# 09_-_FPGA_IO_BANK_2A_2L.net
KiCad netlist of a schematic drawn in Altium Designer
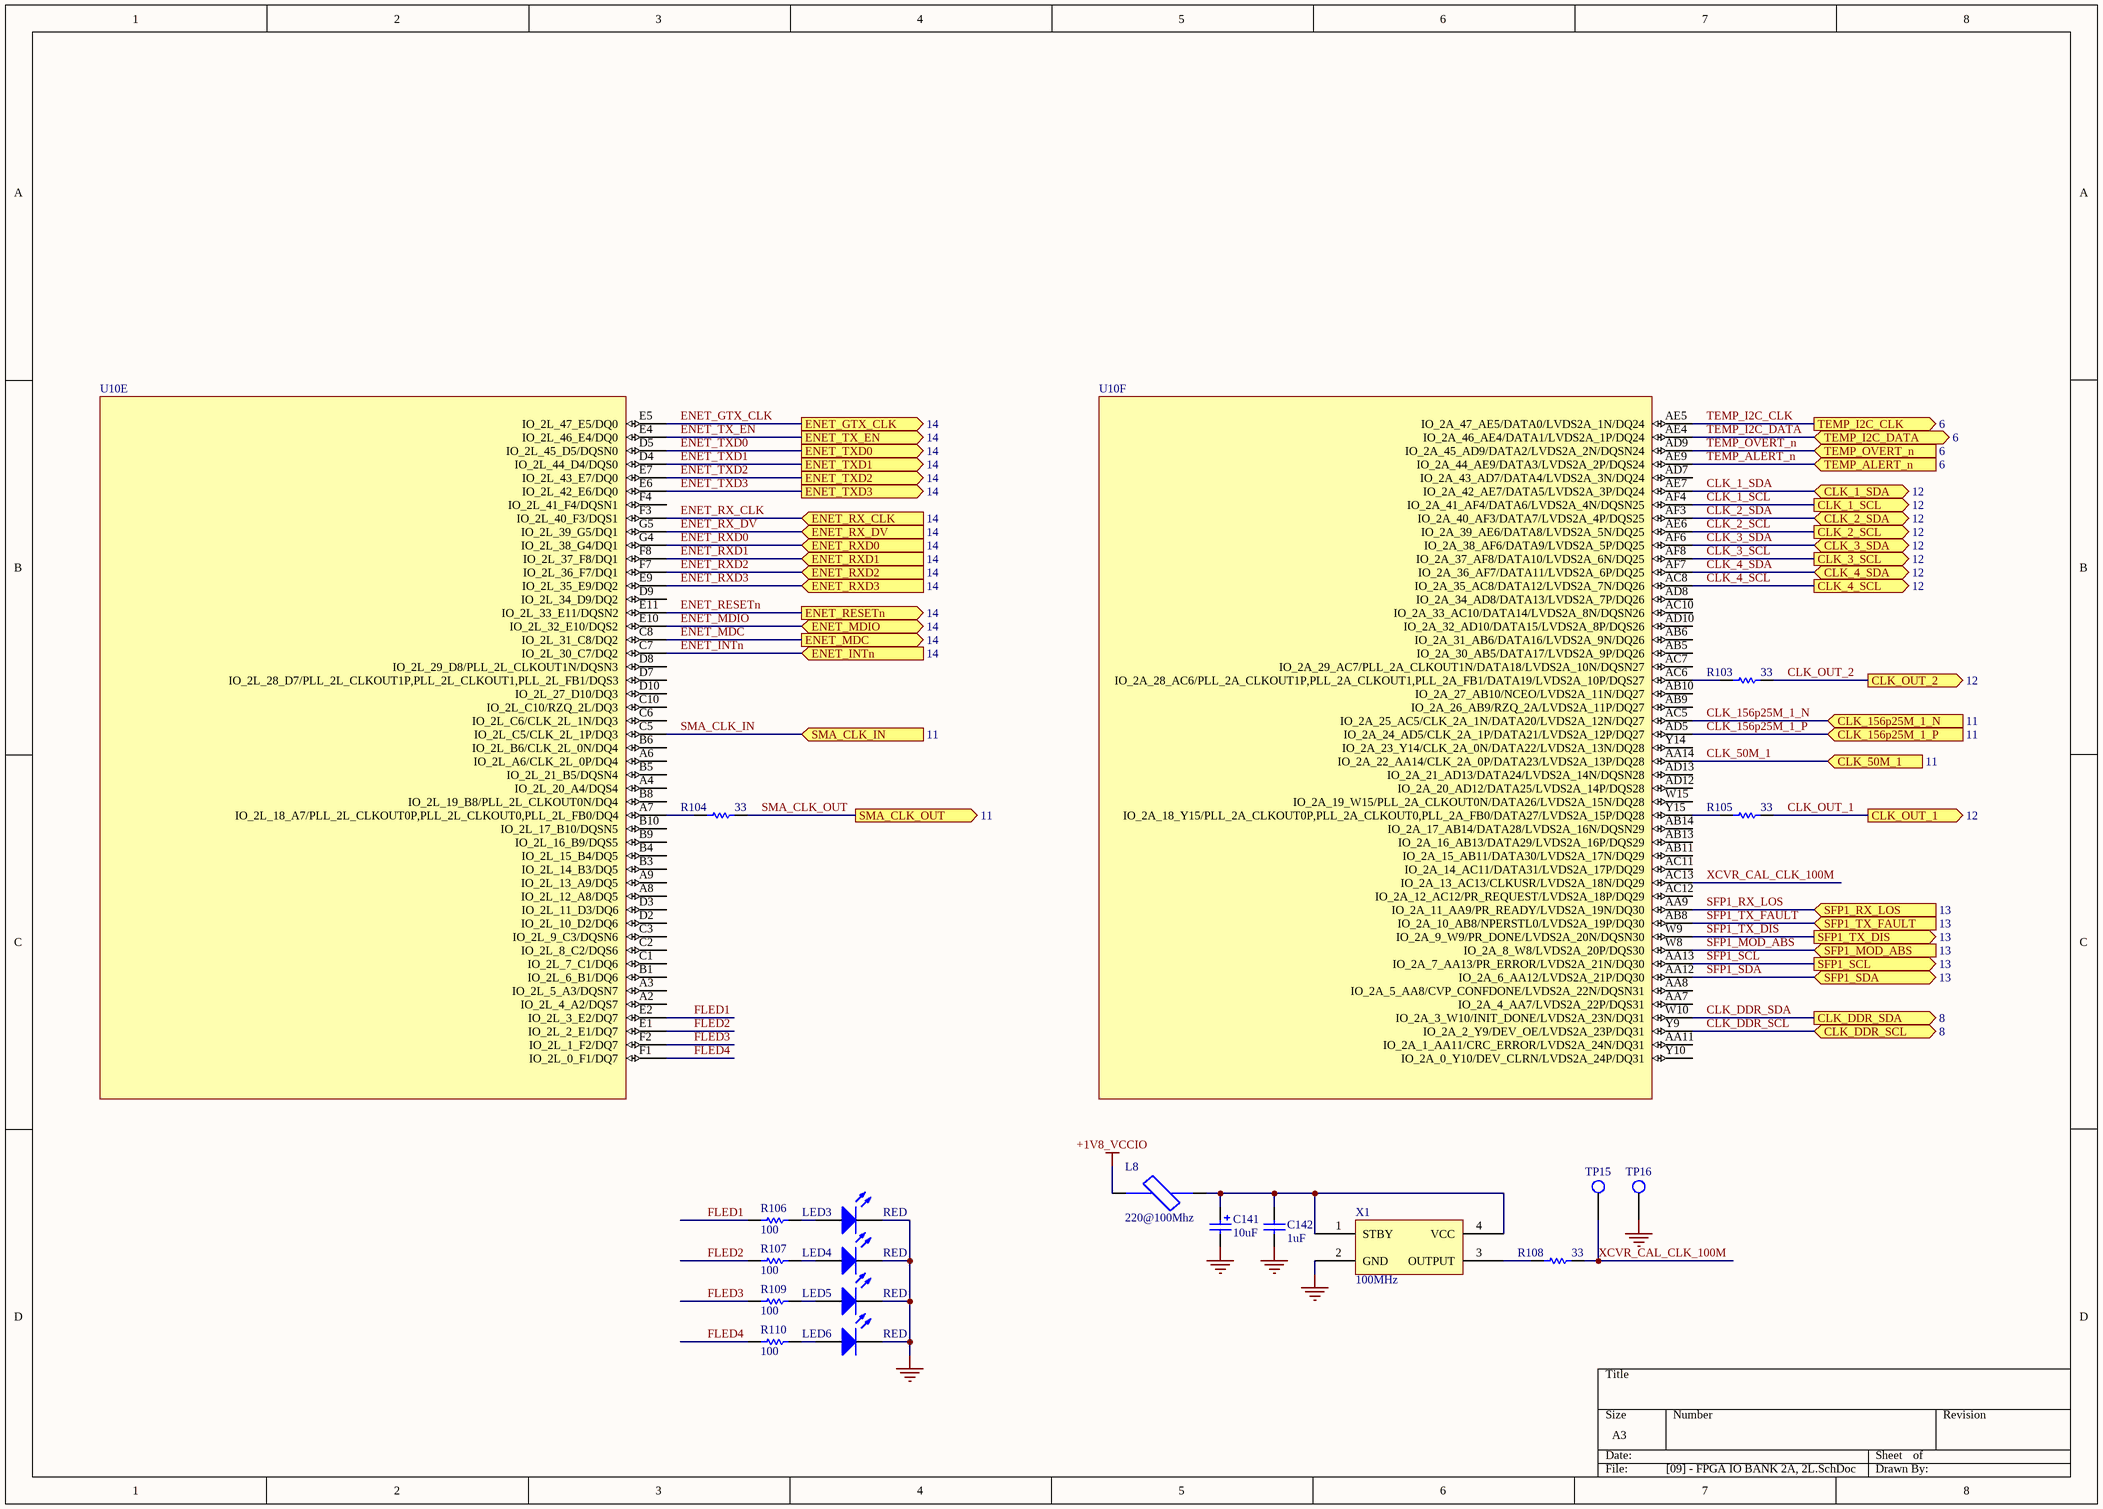
[diagram p0: [09] - FPGA IO BANK 2A, 2L.SchDoc]

(export (version "E")
  (design (tool "Eeschema 10.0.6"))
  (components
    (comp (ref "C141")
      (value "10uF")
      (footprint "TANT_B")
      (description "Tantalum Polarized Capacitor")
      (libsource (lib "Passive Components") (part "Cap Tant"))
    )
    (comp (ref "C142")
      (value "1uF")
      (footprint "0402_C")
      (description "Non-Pol SMD Capacitor")
      (libsource (lib "Passive Components") (part "Cap SMD"))
    )
    (comp (ref "L8")
      (value "220@100Mhz")
      (footprint "0805_L")
      (description "Ferrite Bead")
      (libsource (lib "Passive Components") (part "Ferrite Bead"))
    )
    (comp (ref "LED3")
      (value "RED")
      (footprint "LED_0805")
      (description "Typical LED")
      (libsource (lib "Common Components") (part "LED"))
    )
    (comp (ref "LED4")
      (value "RED")
      (footprint "LED_0805")
      (description "Typical LED")
      (libsource (lib "Common Components") (part "LED"))
    )
    (comp (ref "LED5")
      (value "RED")
      (footprint "LED_0805")
      (description "Typical LED")
      (libsource (lib "Common Components") (part "LED"))
    )
    (comp (ref "LED6")
      (value "RED")
      (footprint "LED_0805")
      (description "Typical LED")
      (libsource (lib "Common Components") (part "LED"))
    )
    (comp (ref "R103")
      (value "33")
      (footprint "0402_R")
      (description "SMD Resistor")
      (fields (field (name "TOLERANCE") "5%"))
      (libsource (lib "Passive Components") (part "Res SMD"))
    )
    (comp (ref "R104")
      (value "33")
      (footprint "0402_R")
      (description "SMD Resistor")
      (fields (field (name "TOLERANCE") "5%"))
      (libsource (lib "Passive Components") (part "Res SMD"))
    )
    (comp (ref "R105")
      (value "33")
      (footprint "0402_R")
      (description "SMD Resistor")
      (fields (field (name "TOLERANCE") "5%"))
      (libsource (lib "Passive Components") (part "Res SMD"))
    )
    (comp (ref "R106")
      (value "100")
      (footprint "0805_R")
      (description "SMD Resistor")
      (fields (field (name "TOLERANCE") "5%"))
      (libsource (lib "Passive Components") (part "Res SMD"))
    )
    (comp (ref "R107")
      (value "100")
      (footprint "0805_R")
      (description "SMD Resistor")
      (fields (field (name "TOLERANCE") "5%"))
      (libsource (lib "Passive Components") (part "Res SMD"))
    )
    (comp (ref "R108")
      (value "33")
      (footprint "0402_R")
      (description "SMD Resistor")
      (fields (field (name "TOLERANCE") "5%"))
      (libsource (lib "Passive Components") (part "Res SMD"))
    )
    (comp (ref "R109")
      (value "100")
      (footprint "0805_R")
      (description "SMD Resistor")
      (fields (field (name "TOLERANCE") "5%"))
      (libsource (lib "Passive Components") (part "Res SMD"))
    )
    (comp (ref "R110")
      (value "100")
      (footprint "0805_R")
      (description "SMD Resistor")
      (fields (field (name "TOLERANCE") "5%"))
      (libsource (lib "Passive Components") (part "Res SMD"))
    )
    (comp (ref "TP15")
      (value "Test Point")
      (footprint "PIN_1mm")
      (description "Test Point Footprint")
      (libsource (lib "Passive Components") (part "Test Point"))
    )
    (comp (ref "TP16")
      (value "Test Point")
      (footprint "PIN_1mm")
      (description "Test Point Footprint")
      (libsource (lib "Passive Components") (part "Test Point"))
    )
    (comp (ref "U10") (value "10AX016 F27") (footprint "FBGA672") (libsource (lib "") (part "10AX016_1")))
    (comp (ref "X1")
      (value "100MHz")
      (footprint "OSC_5X3.2")
      (description "Crystal Oscillator")
      (fields (field (name "MANUFACTURER PART NUM") "ECS-3518-1000-B-TR"))
      (libsource (lib "Common Components") (part "XTAL OSC"))
    )
  )
  (nets
    (net (code "1") (name "+1V8_VCCIO") (class "Default")
      (node (ref "L8") (pin "1") (pinfunction "1_1") (pintype "passive"))
    )
    (net (code "2") (name "/CLK_1_SCL") (class "Default")
      (node (ref "U10") (pin "AF4") (pinfunction "IO_2A_41_AF4/DATA6/LVDS2A_4N/DQSN25_AF4") (pintype "bidirectional"))
    )
    (net (code "3") (name "/CLK_1_SDA") (class "Default")
      (node (ref "U10") (pin "AE7") (pinfunction "IO_2A_42_AE7/DATA5/LVDS2A_3P/DQ24_AE7") (pintype "bidirectional"))
    )
    (net (code "4") (name "/CLK_2_SCL") (class "Default")
      (node (ref "U10") (pin "AE6") (pinfunction "IO_2A_39_AE6/DATA8/LVDS2A_5N/DQ25_AE6") (pintype "bidirectional"))
    )
    (net (code "5") (name "/CLK_2_SDA") (class "Default")
      (node (ref "U10") (pin "AF3") (pinfunction "IO_2A_40_AF3/DATA7/LVDS2A_4P/DQS25_AF3") (pintype "bidirectional"))
    )
    (net (code "6") (name "/CLK_3_SCL") (class "Default")
      (node (ref "U10") (pin "AF8") (pinfunction "IO_2A_37_AF8/DATA10/LVDS2A_6N/DQ25_AF8") (pintype "bidirectional"))
    )
    (net (code "7") (name "/CLK_3_SDA") (class "Default")
      (node (ref "U10") (pin "AF6") (pinfunction "IO_2A_38_AF6/DATA9/LVDS2A_5P/DQ25_AF6") (pintype "bidirectional"))
    )
    (net (code "8") (name "/CLK_4_SCL") (class "Default")
      (node (ref "U10") (pin "AC8") (pinfunction "IO_2A_35_AC8/DATA12/LVDS2A_7N/DQ26_AC8") (pintype "bidirectional"))
    )
    (net (code "9") (name "/CLK_4_SDA") (class "Default")
      (node (ref "U10") (pin "AF7") (pinfunction "IO_2A_36_AF7/DATA11/LVDS2A_6P/DQ25_AF7") (pintype "bidirectional"))
    )
    (net (code "10") (name "/CLK_50M_1") (class "Default")
      (node (ref "U10") (pin "AA14") (pinfunction "IO_2A_22_AA14/CLK_2A_0P/DATA23/LVDS2A_13P/DQ28_AA14") (pintype "bidirectional"))
    )
    (net (code "11") (name "/CLK_156p25M_1_N") (class "Default")
      (node (ref "U10") (pin "AC5") (pinfunction "IO_2A_25_AC5/CLK_2A_1N/DATA20/LVDS2A_12N/DQ27_AC5") (pintype "bidirectional"))
    )
    (net (code "12") (name "/CLK_156p25M_1_P") (class "Default")
      (node (ref "U10") (pin "AD5") (pinfunction "IO_2A_24_AD5/CLK_2A_1P/DATA21/LVDS2A_12P/DQ27_AD5") (pintype "bidirectional"))
    )
    (net (code "13") (name "/CLK_DDR_SCL") (class "Default")
      (node (ref "U10") (pin "Y9") (pinfunction "IO_2A_2_Y9/DEV_OE/LVDS2A_23P/DQ31_Y9") (pintype "bidirectional"))
    )
    (net (code "14") (name "/CLK_DDR_SDA") (class "Default")
      (node (ref "U10") (pin "W10") (pinfunction "IO_2A_3_W10/INIT_DONE/LVDS2A_23N/DQ31_W10") (pintype "bidirectional"))
    )
    (net (code "15") (name "/CLK_OUT_1") (class "Default")
      (node (ref "R105") (pin "2") (pinfunction "2_2") (pintype "passive"))
    )
    (net (code "16") (name "/CLK_OUT_2") (class "Default")
      (node (ref "R103") (pin "2") (pinfunction "2_2") (pintype "passive"))
    )
    (net (code "17") (name "/ENET_GTX_CLK") (class "Default")
      (node (ref "U10") (pin "E5") (pinfunction "IO_2L_47_E5/DQ0_E5") (pintype "bidirectional"))
    )
    (net (code "18") (name "/ENET_INTn") (class "Default")
      (node (ref "U10") (pin "C7") (pinfunction "IO_2L_30_C7/DQ2_C7") (pintype "bidirectional"))
    )
    (net (code "19") (name "/ENET_MDC") (class "Default")
      (node (ref "U10") (pin "C8") (pinfunction "IO_2L_31_C8/DQ2_C8") (pintype "bidirectional"))
    )
    (net (code "20") (name "/ENET_MDIO") (class "Default")
      (node (ref "U10") (pin "E10") (pinfunction "IO_2L_32_E10/DQS2_E10") (pintype "bidirectional"))
    )
    (net (code "21") (name "/ENET_RESETn") (class "Default")
      (node (ref "U10") (pin "E11") (pinfunction "IO_2L_33_E11/DQSN2_E11") (pintype "bidirectional"))
    )
    (net (code "22") (name "/ENET_RXD0") (class "Default")
      (node (ref "U10") (pin "G4") (pinfunction "IO_2L_38_G4/DQ1_G4") (pintype "bidirectional"))
    )
    (net (code "23") (name "/ENET_RXD1") (class "Default")
      (node (ref "U10") (pin "F8") (pinfunction "IO_2L_37_F8/DQ1_F8") (pintype "bidirectional"))
    )
    (net (code "24") (name "/ENET_RXD2") (class "Default")
      (node (ref "U10") (pin "F7") (pinfunction "IO_2L_36_F7/DQ1_F7") (pintype "bidirectional"))
    )
    (net (code "25") (name "/ENET_RXD3") (class "Default")
      (node (ref "U10") (pin "E9") (pinfunction "IO_2L_35_E9/DQ2_E9") (pintype "bidirectional"))
    )
    (net (code "26") (name "/ENET_RX_CLK") (class "Default")
      (node (ref "U10") (pin "F3") (pinfunction "IO_2L_40_F3/DQS1_F3") (pintype "bidirectional"))
    )
    (net (code "27") (name "/ENET_RX_DV") (class "Default")
      (node (ref "U10") (pin "G5") (pinfunction "IO_2L_39_G5/DQ1_G5") (pintype "bidirectional"))
    )
    (net (code "28") (name "/ENET_TXD0") (class "Default")
      (node (ref "U10") (pin "D5") (pinfunction "IO_2L_45_D5/DQSN0_D5") (pintype "bidirectional"))
    )
    (net (code "29") (name "/ENET_TXD1") (class "Default")
      (node (ref "U10") (pin "D4") (pinfunction "IO_2L_44_D4/DQS0_D4") (pintype "bidirectional"))
    )
    (net (code "30") (name "/ENET_TXD2") (class "Default")
      (node (ref "U10") (pin "E7") (pinfunction "IO_2L_43_E7/DQ0_E7") (pintype "bidirectional"))
    )
    (net (code "31") (name "/ENET_TXD3") (class "Default")
      (node (ref "U10") (pin "E6") (pinfunction "IO_2L_42_E6/DQ0_E6") (pintype "bidirectional"))
    )
    (net (code "32") (name "/ENET_TX_EN") (class "Default")
      (node (ref "U10") (pin "E4") (pinfunction "IO_2L_46_E4/DQ0_E4") (pintype "bidirectional"))
    )
    (net (code "33") (name "/FLED1") (class "Default")
      (node (ref "R106") (pin "2") (pinfunction "2_2") (pintype "passive"))
      (node (ref "U10") (pin "E2") (pinfunction "IO_2L_3_E2/DQ7_E2") (pintype "bidirectional"))
    )
    (net (code "34") (name "/FLED2") (class "Default")
      (node (ref "R107") (pin "2") (pinfunction "2_2") (pintype "passive"))
      (node (ref "U10") (pin "E1") (pinfunction "IO_2L_2_E1/DQ7_E1") (pintype "bidirectional"))
    )
    (net (code "35") (name "/FLED3") (class "Default")
      (node (ref "R109") (pin "2") (pinfunction "2_2") (pintype "passive"))
      (node (ref "U10") (pin "F2") (pinfunction "IO_2L_1_F2/DQ7_F2") (pintype "bidirectional"))
    )
    (net (code "36") (name "/FLED4") (class "Default")
      (node (ref "R110") (pin "2") (pinfunction "2_2") (pintype "passive"))
      (node (ref "U10") (pin "F1") (pinfunction "IO_2L_0_F1/DQ7_F1") (pintype "bidirectional"))
    )
    (net (code "37") (name "/SFP1_MOD_ABS") (class "Default")
      (node (ref "U10") (pin "W8") (pinfunction "IO_2A_8_W8/LVDS2A_20P/DQS30_W8") (pintype "bidirectional"))
    )
    (net (code "38") (name "/SFP1_RX_LOS") (class "Default")
      (node (ref "U10") (pin "AA9") (pinfunction "IO_2A_11_AA9/PR_READY/LVDS2A_19N/DQ30_AA9") (pintype "bidirectional"))
    )
    (net (code "39") (name "/SFP1_SCL") (class "Default")
      (node (ref "U10") (pin "AA13") (pinfunction "IO_2A_7_AA13/PR_ERROR/LVDS2A_21N/DQ30_AA13") (pintype "bidirectional"))
    )
    (net (code "40") (name "/SFP1_SDA") (class "Default")
      (node (ref "U10") (pin "AA12") (pinfunction "IO_2A_6_AA12/LVDS2A_21P/DQ30_AA12") (pintype "bidirectional"))
    )
    (net (code "41") (name "/SFP1_TX_DIS") (class "Default")
      (node (ref "U10") (pin "W9") (pinfunction "IO_2A_9_W9/PR_DONE/LVDS2A_20N/DQSN30_W9") (pintype "bidirectional"))
    )
    (net (code "42") (name "/SFP1_TX_FAULT") (class "Default")
      (node (ref "U10") (pin "AB8") (pinfunction "IO_2A_10_AB8/NPERSTL0/LVDS2A_19P/DQ30_AB8") (pintype "bidirectional"))
    )
    (net (code "43") (name "/SMA_CLK_IN") (class "Default")
      (node (ref "U10") (pin "C5") (pinfunction "IO_2L_C5/CLK_2L_1P/DQ3_C5") (pintype "bidirectional"))
    )
    (net (code "44") (name "/SMA_CLK_OUT") (class "Default")
      (node (ref "R104") (pin "2") (pinfunction "2_2") (pintype "passive"))
    )
    (net (code "45") (name "/TEMP_ALERT_n") (class "Default")
      (node (ref "U10") (pin "AE9") (pinfunction "IO_2A_44_AE9/DATA3/LVDS2A_2P/DQS24_AE9") (pintype "bidirectional"))
    )
    (net (code "46") (name "/TEMP_I2C_CLK") (class "Default")
      (node (ref "U10") (pin "AE5") (pinfunction "IO_2A_47_AE5/DATA0/LVDS2A_1N/DQ24_AE5") (pintype "bidirectional"))
    )
    (net (code "47") (name "/TEMP_I2C_DATA") (class "Default")
      (node (ref "U10") (pin "AE4") (pinfunction "IO_2A_46_AE4/DATA1/LVDS2A_1P/DQ24_AE4") (pintype "bidirectional"))
    )
    (net (code "48") (name "/TEMP_OVERT_n") (class "Default")
      (node (ref "U10") (pin "AD9") (pinfunction "IO_2A_45_AD9/DATA2/LVDS2A_2N/DQSN24_AD9") (pintype "bidirectional"))
    )
    (net (code "49") (name "/XCVR_CAL_CLK_100M") (class "Default")
      (node (ref "R108") (pin "2") (pinfunction "2_2") (pintype "passive"))
      (node (ref "TP15") (pin "1") (pinfunction "1_1") (pintype "passive"))
      (node (ref "U10") (pin "AC13") (pinfunction "IO_2A_13_AC13/CLKUSR/LVDS2A_18N/DQ29_AC13") (pintype "bidirectional"))
    )
    (net (code "50") (name "GND") (class "Default")
      (node (ref "C141") (pin "2") (pinfunction "2_2") (pintype "passive"))
      (node (ref "C142") (pin "1") (pinfunction "1_1") (pintype "passive"))
      (node (ref "LED3") (pin "2") (pinfunction "K_2") (pintype "passive"))
      (node (ref "LED4") (pin "2") (pinfunction "K_2") (pintype "passive"))
      (node (ref "LED5") (pin "2") (pinfunction "K_2") (pintype "passive"))
      (node (ref "LED6") (pin "2") (pinfunction "K_2") (pintype "passive"))
      (node (ref "TP16") (pin "1") (pinfunction "1_1") (pintype "passive"))
      (node (ref "X1") (pin "2") (pinfunction "GND_2") (pintype "passive"))
    )
    (net (code "51") (name "Net-(LED3-A)") (class "Default")
      (node (ref "LED3") (pin "1") (pinfunction "A_1") (pintype "passive"))
      (node (ref "R106") (pin "1") (pinfunction "1_1") (pintype "passive"))
    )
    (net (code "52") (name "Net-(LED4-A)") (class "Default")
      (node (ref "LED4") (pin "1") (pinfunction "A_1") (pintype "passive"))
      (node (ref "R107") (pin "1") (pinfunction "1_1") (pintype "passive"))
    )
    (net (code "53") (name "Net-(LED5-A)") (class "Default")
      (node (ref "LED5") (pin "1") (pinfunction "A_1") (pintype "passive"))
      (node (ref "R109") (pin "1") (pinfunction "1_1") (pintype "passive"))
    )
    (net (code "54") (name "Net-(LED6-A)") (class "Default")
      (node (ref "LED6") (pin "1") (pinfunction "A_1") (pintype "passive"))
      (node (ref "R110") (pin "1") (pinfunction "1_1") (pintype "passive"))
    )
    (net (code "55") (name "Net-(U10E-IO_2L_18_A7{slash}PLL_2L_CLKOUT0P,PLL_2L_CLKOUT0,PLL_2L_FB0{slash}DQ4)") (class "Default")
      (node (ref "R104") (pin "1") (pinfunction "1_1") (pintype "passive"))
      (node (ref "U10") (pin "A7") (pinfunction "IO_2L_18_A7/PLL_2L_CLKOUT0P,PLL_2L_CLKOUT0,PLL_2L_FB0/DQ4_A7") (pintype "bidirectional"))
    )
    (net (code "56") (name "Net-(U10F-IO_2A_18_Y15{slash}PLL_2A_CLKOUT0P,PLL_2A_CLKOUT0,PLL_2A_FB0{slash}DATA27{slash}LVDS2A_15P{slash}DQ28)") (class "Default")
      (node (ref "R105") (pin "1") (pinfunction "1_1") (pintype "passive"))
      (node (ref "U10") (pin "Y15") (pinfunction "IO_2A_18_Y15/PLL_2A_CLKOUT0P,PLL_2A_CLKOUT0,PLL_2A_FB0/DATA27/LVDS2A_15P/DQ28_Y15") (pintype "bidirectional"))
    )
    (net (code "57") (name "Net-(U10F-IO_2A_28_AC6{slash}PLL_2A_CLKOUT1P,PLL_2A_CLKOUT1,PLL_2A_FB1{slash}DATA19{slash}LVDS2A_10P{slash}DQS27)") (class "Default")
      (node (ref "R103") (pin "1") (pinfunction "1_1") (pintype "passive"))
      (node (ref "U10") (pin "AC6") (pinfunction "IO_2A_28_AC6/PLL_2A_CLKOUT1P,PLL_2A_CLKOUT1,PLL_2A_FB1/DATA19/LVDS2A_10P/DQS27_AC6") (pintype "bidirectional"))
    )
    (net (code "58") (name "Net-(X1-OUTPUT)") (class "Default")
      (node (ref "R108") (pin "1") (pinfunction "1_1") (pintype "passive"))
      (node (ref "X1") (pin "3") (pinfunction "OUTPUT_3") (pintype "passive"))
    )
    (net (code "59") (name "Net-(X1-STBY)") (class "Default")
      (node (ref "C141") (pin "1") (pinfunction "1_1") (pintype "passive"))
      (node (ref "C142") (pin "2") (pinfunction "2_2") (pintype "passive"))
      (node (ref "L8") (pin "2") (pinfunction "2_2") (pintype "passive"))
      (node (ref "X1") (pin "1") (pinfunction "STBY_1") (pintype "passive"))
      (node (ref "X1") (pin "4") (pinfunction "VCC_4") (pintype "passive"))
    )
    (net (code "60") (name "unconnected-(U10E-IO_2L_4_A2{slash}DQS7-PadA2)") (class "Default")
      (node (ref "U10") (pin "A2") (pinfunction "IO_2L_4_A2/DQS7_A2") (pintype "bidirectional"))
    )
    (net (code "61") (name "unconnected-(U10E-IO_2L_5_A3{slash}DQSN7-PadA3)") (class "Default")
      (node (ref "U10") (pin "A3") (pinfunction "IO_2L_5_A3/DQSN7_A3") (pintype "bidirectional"))
    )
    (net (code "62") (name "unconnected-(U10E-IO_2L_6_B1{slash}DQ6-PadB1)") (class "Default")
      (node (ref "U10") (pin "B1") (pinfunction "IO_2L_6_B1/DQ6_B1") (pintype "bidirectional"))
    )
    (net (code "63") (name "unconnected-(U10E-IO_2L_7_C1{slash}DQ6-PadC1)") (class "Default")
      (node (ref "U10") (pin "C1") (pinfunction "IO_2L_7_C1/DQ6_C1") (pintype "bidirectional"))
    )
    (net (code "64") (name "unconnected-(U10E-IO_2L_8_C2{slash}DQS6-PadC2)") (class "Default")
      (node (ref "U10") (pin "C2") (pinfunction "IO_2L_8_C2/DQS6_C2") (pintype "bidirectional"))
    )
    (net (code "65") (name "unconnected-(U10E-IO_2L_9_C3{slash}DQSN6-PadC3)") (class "Default")
      (node (ref "U10") (pin "C3") (pinfunction "IO_2L_9_C3/DQSN6_C3") (pintype "bidirectional"))
    )
    (net (code "66") (name "unconnected-(U10E-IO_2L_10_D2{slash}DQ6-PadD2)") (class "Default")
      (node (ref "U10") (pin "D2") (pinfunction "IO_2L_10_D2/DQ6_D2") (pintype "bidirectional"))
    )
    (net (code "67") (name "unconnected-(U10E-IO_2L_11_D3{slash}DQ6-PadD3)") (class "Default")
      (node (ref "U10") (pin "D3") (pinfunction "IO_2L_11_D3/DQ6_D3") (pintype "bidirectional"))
    )
    (net (code "68") (name "unconnected-(U10E-IO_2L_12_A8{slash}DQ5-PadA8)") (class "Default")
      (node (ref "U10") (pin "A8") (pinfunction "IO_2L_12_A8/DQ5_A8") (pintype "bidirectional"))
    )
    (net (code "69") (name "unconnected-(U10E-IO_2L_13_A9{slash}DQ5-PadA9)") (class "Default")
      (node (ref "U10") (pin "A9") (pinfunction "IO_2L_13_A9/DQ5_A9") (pintype "bidirectional"))
    )
    (net (code "70") (name "unconnected-(U10E-IO_2L_14_B3{slash}DQ5-PadB3)") (class "Default")
      (node (ref "U10") (pin "B3") (pinfunction "IO_2L_14_B3/DQ5_B3") (pintype "bidirectional"))
    )
    (net (code "71") (name "unconnected-(U10E-IO_2L_15_B4{slash}DQ5-PadB4)") (class "Default")
      (node (ref "U10") (pin "B4") (pinfunction "IO_2L_15_B4/DQ5_B4") (pintype "bidirectional"))
    )
    (net (code "72") (name "unconnected-(U10E-IO_2L_16_B9{slash}DQS5-PadB9)") (class "Default")
      (node (ref "U10") (pin "B9") (pinfunction "IO_2L_16_B9/DQS5_B9") (pintype "bidirectional"))
    )
    (net (code "73") (name "unconnected-(U10E-IO_2L_17_B10{slash}DQSN5-PadB10)") (class "Default")
      (node (ref "U10") (pin "B10") (pinfunction "IO_2L_17_B10/DQSN5_B10") (pintype "bidirectional"))
    )
    (net (code "74") (name "unconnected-(U10E-IO_2L_19_B8{slash}PLL_2L_CLKOUT0N{slash}DQ4-PadB8)") (class "Default")
      (node (ref "U10") (pin "B8") (pinfunction "IO_2L_19_B8/PLL_2L_CLKOUT0N/DQ4_B8") (pintype "bidirectional"))
    )
    (net (code "75") (name "unconnected-(U10E-IO_2L_20_A4{slash}DQS4-PadA4)") (class "Default")
      (node (ref "U10") (pin "A4") (pinfunction "IO_2L_20_A4/DQS4_A4") (pintype "bidirectional"))
    )
    (net (code "76") (name "unconnected-(U10E-IO_2L_21_B5{slash}DQSN4-PadB5)") (class "Default")
      (node (ref "U10") (pin "B5") (pinfunction "IO_2L_21_B5/DQSN4_B5") (pintype "bidirectional"))
    )
    (net (code "77") (name "unconnected-(U10E-IO_2L_27_D10{slash}DQ3-PadD10)") (class "Default")
      (node (ref "U10") (pin "D10") (pinfunction "IO_2L_27_D10/DQ3_D10") (pintype "bidirectional"))
    )
    (net (code "78") (name "unconnected-(U10E-IO_2L_28_D7{slash}PLL_2L_CLKOUT1P,PLL_2L_CLKOUT1,PLL_2L_FB1{slash}DQS3-PadD7)") (class "Default")
      (node (ref "U10") (pin "D7") (pinfunction "IO_2L_28_D7/PLL_2L_CLKOUT1P,PLL_2L_CLKOUT1,PLL_2L_FB1/DQS3_D7") (pintype "bidirectional"))
    )
    (net (code "79") (name "unconnected-(U10E-IO_2L_29_D8{slash}PLL_2L_CLKOUT1N{slash}DQSN3-PadD8)") (class "Default")
      (node (ref "U10") (pin "D8") (pinfunction "IO_2L_29_D8/PLL_2L_CLKOUT1N/DQSN3_D8") (pintype "bidirectional"))
    )
    (net (code "80") (name "unconnected-(U10E-IO_2L_34_D9{slash}DQ2-PadD9)") (class "Default")
      (node (ref "U10") (pin "D9") (pinfunction "IO_2L_34_D9/DQ2_D9") (pintype "bidirectional"))
    )
    (net (code "81") (name "unconnected-(U10E-IO_2L_41_F4{slash}DQSN1-PadF4)") (class "Default")
      (node (ref "U10") (pin "F4") (pinfunction "IO_2L_41_F4/DQSN1_F4") (pintype "bidirectional"))
    )
    (net (code "82") (name "unconnected-(U10E-IO_2L_A6{slash}CLK_2L_0P{slash}DQ4-PadA6)") (class "Default")
      (node (ref "U10") (pin "A6") (pinfunction "IO_2L_A6/CLK_2L_0P/DQ4_A6") (pintype "bidirectional"))
    )
    (net (code "83") (name "unconnected-(U10E-IO_2L_B6{slash}CLK_2L_0N{slash}DQ4-PadB6)") (class "Default")
      (node (ref "U10") (pin "B6") (pinfunction "IO_2L_B6/CLK_2L_0N/DQ4_B6") (pintype "bidirectional"))
    )
    (net (code "84") (name "unconnected-(U10E-IO_2L_C6{slash}CLK_2L_1N{slash}DQ3-PadC6)") (class "Default")
      (node (ref "U10") (pin "C6") (pinfunction "IO_2L_C6/CLK_2L_1N/DQ3_C6") (pintype "bidirectional"))
    )
    (net (code "85") (name "unconnected-(U10E-IO_2L_C10{slash}RZQ_2L{slash}DQ3-PadC10)") (class "Default")
      (node (ref "U10") (pin "C10") (pinfunction "IO_2L_C10/RZQ_2L/DQ3_C10") (pintype "bidirectional"))
    )
    (net (code "86") (name "unconnected-(U10F-IO_2A_0_Y10{slash}DEV_CLRN{slash}LVDS2A_24P{slash}DQ31-PadY10)") (class "Default")
      (node (ref "U10") (pin "Y10") (pinfunction "IO_2A_0_Y10/DEV_CLRN/LVDS2A_24P/DQ31_Y10") (pintype "bidirectional"))
    )
    (net (code "87") (name "unconnected-(U10F-IO_2A_1_AA11{slash}CRC_ERROR{slash}LVDS2A_24N{slash}DQ31-PadAA11)") (class "Default")
      (node (ref "U10") (pin "AA11") (pinfunction "IO_2A_1_AA11/CRC_ERROR/LVDS2A_24N/DQ31_AA11") (pintype "bidirectional"))
    )
    (net (code "88") (name "unconnected-(U10F-IO_2A_4_AA7{slash}LVDS2A_22P{slash}DQS31-PadAA7)") (class "Default")
      (node (ref "U10") (pin "AA7") (pinfunction "IO_2A_4_AA7/LVDS2A_22P/DQS31_AA7") (pintype "bidirectional"))
    )
    (net (code "89") (name "unconnected-(U10F-IO_2A_5_AA8{slash}CVP_CONFDONE{slash}LVDS2A_22N{slash}DQSN31-PadAA8)") (class "Default")
      (node (ref "U10") (pin "AA8") (pinfunction "IO_2A_5_AA8/CVP_CONFDONE/LVDS2A_22N/DQSN31_AA8") (pintype "bidirectional"))
    )
    (net (code "90") (name "unconnected-(U10F-IO_2A_12_AC12{slash}PR_REQUEST{slash}LVDS2A_18P{slash}DQ29-PadAC12)") (class "Default")
      (node (ref "U10") (pin "AC12") (pinfunction "IO_2A_12_AC12/PR_REQUEST/LVDS2A_18P/DQ29_AC12") (pintype "bidirectional"))
    )
    (net (code "91") (name "unconnected-(U10F-IO_2A_14_AC11{slash}DATA31{slash}LVDS2A_17P{slash}DQ29-PadAC11)") (class "Default")
      (node (ref "U10") (pin "AC11") (pinfunction "IO_2A_14_AC11/DATA31/LVDS2A_17P/DQ29_AC11") (pintype "bidirectional"))
    )
    (net (code "92") (name "unconnected-(U10F-IO_2A_15_AB11{slash}DATA30{slash}LVDS2A_17N{slash}DQ29-PadAB11)") (class "Default")
      (node (ref "U10") (pin "AB11") (pinfunction "IO_2A_15_AB11/DATA30/LVDS2A_17N/DQ29_AB11") (pintype "bidirectional"))
    )
    (net (code "93") (name "unconnected-(U10F-IO_2A_16_AB13{slash}DATA29{slash}LVDS2A_16P{slash}DQS29-PadAB13)") (class "Default")
      (node (ref "U10") (pin "AB13") (pinfunction "IO_2A_16_AB13/DATA29/LVDS2A_16P/DQS29_AB13") (pintype "bidirectional"))
    )
    (net (code "94") (name "unconnected-(U10F-IO_2A_17_AB14{slash}DATA28{slash}LVDS2A_16N{slash}DQSN29-PadAB14)") (class "Default")
      (node (ref "U10") (pin "AB14") (pinfunction "IO_2A_17_AB14/DATA28/LVDS2A_16N/DQSN29_AB14") (pintype "bidirectional"))
    )
    (net (code "95") (name "unconnected-(U10F-IO_2A_19_W15{slash}PLL_2A_CLKOUT0N{slash}DATA26{slash}LVDS2A_15N{slash}DQ28-PadW15)") (class "Default")
      (node (ref "U10") (pin "W15") (pinfunction "IO_2A_19_W15/PLL_2A_CLKOUT0N/DATA26/LVDS2A_15N/DQ28_W15") (pintype "bidirectional"))
    )
    (net (code "96") (name "unconnected-(U10F-IO_2A_20_AD12{slash}DATA25{slash}LVDS2A_14P{slash}DQS28-PadAD12)") (class "Default")
      (node (ref "U10") (pin "AD12") (pinfunction "IO_2A_20_AD12/DATA25/LVDS2A_14P/DQS28_AD12") (pintype "bidirectional"))
    )
    (net (code "97") (name "unconnected-(U10F-IO_2A_21_AD13{slash}DATA24{slash}LVDS2A_14N{slash}DQSN28-PadAD13)") (class "Default")
      (node (ref "U10") (pin "AD13") (pinfunction "IO_2A_21_AD13/DATA24/LVDS2A_14N/DQSN28_AD13") (pintype "bidirectional"))
    )
    (net (code "98") (name "unconnected-(U10F-IO_2A_23_Y14{slash}CLK_2A_0N{slash}DATA22{slash}LVDS2A_13N{slash}DQ28-PadY14)") (class "Default")
      (node (ref "U10") (pin "Y14") (pinfunction "IO_2A_23_Y14/CLK_2A_0N/DATA22/LVDS2A_13N/DQ28_Y14") (pintype "bidirectional"))
    )
    (net (code "99") (name "unconnected-(U10F-IO_2A_26_AB9{slash}RZQ_2A{slash}LVDS2A_11P{slash}DQ27-PadAB9)") (class "Default")
      (node (ref "U10") (pin "AB9") (pinfunction "IO_2A_26_AB9/RZQ_2A/LVDS2A_11P/DQ27_AB9") (pintype "bidirectional"))
    )
    (net (code "100") (name "unconnected-(U10F-IO_2A_27_AB10{slash}NCEO{slash}LVDS2A_11N{slash}DQ27-PadAB10)") (class "Default")
      (node (ref "U10") (pin "AB10") (pinfunction "IO_2A_27_AB10/NCEO/LVDS2A_11N/DQ27_AB10") (pintype "bidirectional"))
    )
    (net (code "101") (name "unconnected-(U10F-IO_2A_29_AC7{slash}PLL_2A_CLKOUT1N{slash}DATA18{slash}LVDS2A_10N{slash}DQSN27-PadAC7)") (class "Default")
      (node (ref "U10") (pin "AC7") (pinfunction "IO_2A_29_AC7/PLL_2A_CLKOUT1N/DATA18/LVDS2A_10N/DQSN27_AC7") (pintype "bidirectional"))
    )
    (net (code "102") (name "unconnected-(U10F-IO_2A_30_AB5{slash}DATA17{slash}LVDS2A_9P{slash}DQ26-PadAB5)") (class "Default")
      (node (ref "U10") (pin "AB5") (pinfunction "IO_2A_30_AB5/DATA17/LVDS2A_9P/DQ26_AB5") (pintype "bidirectional"))
    )
    (net (code "103") (name "unconnected-(U10F-IO_2A_31_AB6{slash}DATA16{slash}LVDS2A_9N{slash}DQ26-PadAB6)") (class "Default")
      (node (ref "U10") (pin "AB6") (pinfunction "IO_2A_31_AB6/DATA16/LVDS2A_9N/DQ26_AB6") (pintype "bidirectional"))
    )
    (net (code "104") (name "unconnected-(U10F-IO_2A_32_AD10{slash}DATA15{slash}LVDS2A_8P{slash}DQS26-PadAD10)") (class "Default")
      (node (ref "U10") (pin "AD10") (pinfunction "IO_2A_32_AD10/DATA15/LVDS2A_8P/DQS26_AD10") (pintype "bidirectional"))
    )
    (net (code "105") (name "unconnected-(U10F-IO_2A_33_AC10{slash}DATA14{slash}LVDS2A_8N{slash}DQSN26-PadAC10)") (class "Default")
      (node (ref "U10") (pin "AC10") (pinfunction "IO_2A_33_AC10/DATA14/LVDS2A_8N/DQSN26_AC10") (pintype "bidirectional"))
    )
    (net (code "106") (name "unconnected-(U10F-IO_2A_34_AD8{slash}DATA13{slash}LVDS2A_7P{slash}DQ26-PadAD8)") (class "Default")
      (node (ref "U10") (pin "AD8") (pinfunction "IO_2A_34_AD8/DATA13/LVDS2A_7P/DQ26_AD8") (pintype "bidirectional"))
    )
    (net (code "107") (name "unconnected-(U10F-IO_2A_43_AD7{slash}DATA4{slash}LVDS2A_3N{slash}DQ24-PadAD7)") (class "Default")
      (node (ref "U10") (pin "AD7") (pinfunction "IO_2A_43_AD7/DATA4/LVDS2A_3N/DQ24_AD7") (pintype "bidirectional"))
    )
  )
)
